# epm_control_1.net
KiCad netlist of a schematic drawn in Altium Designer
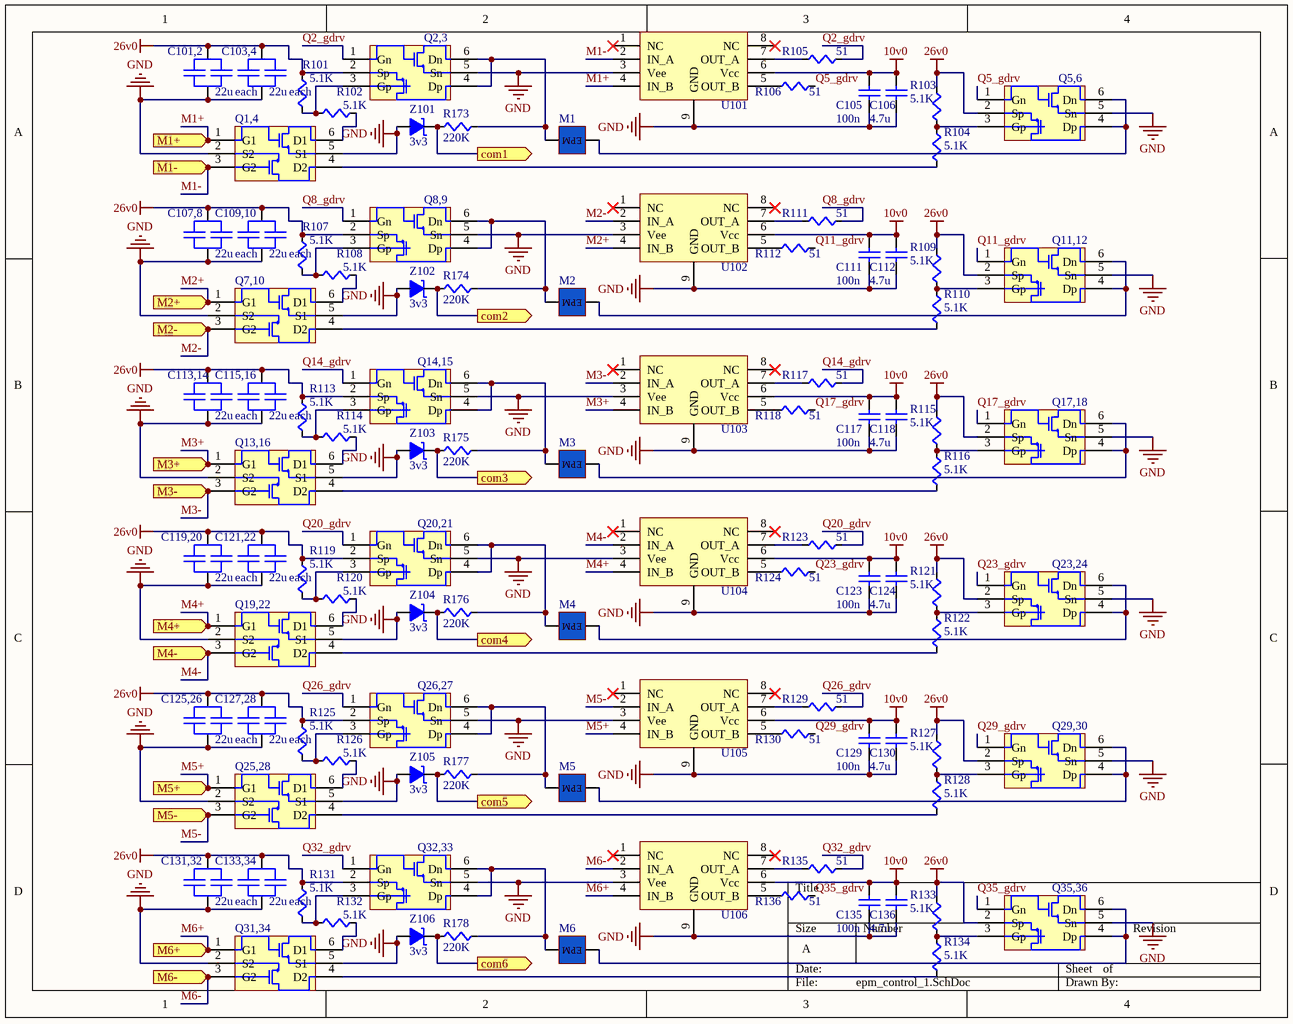
[diagram p0: epm_control_1.SchDoc]

(export (version "E")
  (design (tool "Eeschema 10.0.6"))
  (components
    (comp (ref "C101,2")
      (value "22u")
      (footprint "dicap_smd_1206")
      (fields (field (name "Comment") "Dicap"))
      (libsource (lib "Components") (part "Dicap"))
    )
    (comp (ref "C103,4")
      (value "22u")
      (footprint "dicap_smd_1206")
      (fields (field (name "Comment") "Dicap"))
      (libsource (lib "Components") (part "Dicap"))
    )
    (comp (ref "C105")
      (value "100n")
      (footprint "SMD0603_cap")
      (description "Ceramic Chip Capacitor")
      (fields (field (name "Comment") "Cap"))
      (libsource (lib "Components") (part "Capacitor Ceramic"))
    )
    (comp (ref "C106")
      (value "4.7u")
      (footprint "SMD0603_cap")
      (description "Ceramic Chip Capacitor")
      (fields (field (name "Comment") "Cap"))
      (libsource (lib "Components") (part "Capacitor Ceramic"))
    )
    (comp (ref "C107,8")
      (value "22u")
      (footprint "dicap_smd_1206")
      (fields (field (name "Comment") "Dicap"))
      (libsource (lib "Components") (part "Dicap"))
    )
    (comp (ref "C109,10")
      (value "22u")
      (footprint "dicap_smd_1206")
      (fields (field (name "Comment") "Dicap"))
      (libsource (lib "Components") (part "Dicap"))
    )
    (comp (ref "C111")
      (value "100n")
      (footprint "SMD0603_cap")
      (description "Ceramic Chip Capacitor")
      (fields (field (name "Comment") "Cap"))
      (libsource (lib "Components") (part "Capacitor Ceramic"))
    )
    (comp (ref "C112")
      (value "4.7u")
      (footprint "SMD0603_cap")
      (description "Ceramic Chip Capacitor")
      (fields (field (name "Comment") "Cap"))
      (libsource (lib "Components") (part "Capacitor Ceramic"))
    )
    (comp (ref "C113,14")
      (value "22u")
      (footprint "dicap_smd_1206")
      (fields (field (name "Comment") "Dicap"))
      (libsource (lib "Components") (part "Dicap"))
    )
    (comp (ref "C115,16")
      (value "22u")
      (footprint "dicap_smd_1206")
      (fields (field (name "Comment") "Dicap"))
      (libsource (lib "Components") (part "Dicap"))
    )
    (comp (ref "C117")
      (value "100n")
      (footprint "SMD0603_cap")
      (description "Ceramic Chip Capacitor")
      (fields (field (name "Comment") "Cap"))
      (libsource (lib "Components") (part "Capacitor Ceramic"))
    )
    (comp (ref "C118")
      (value "4.7u")
      (footprint "SMD0603_cap")
      (description "Ceramic Chip Capacitor")
      (fields (field (name "Comment") "Cap"))
      (libsource (lib "Components") (part "Capacitor Ceramic"))
    )
    (comp (ref "C119,20")
      (value "22u")
      (footprint "dicap_smd_1206")
      (fields (field (name "Comment") "Dicap"))
      (libsource (lib "Components") (part "Dicap"))
    )
    (comp (ref "C121,22")
      (value "22u")
      (footprint "dicap_smd_1206")
      (fields (field (name "Comment") "Dicap"))
      (libsource (lib "Components") (part "Dicap"))
    )
    (comp (ref "C123")
      (value "100n")
      (footprint "SMD0603_cap")
      (description "Ceramic Chip Capacitor")
      (fields (field (name "Comment") "Cap"))
      (libsource (lib "Components") (part "Capacitor Ceramic"))
    )
    (comp (ref "C124")
      (value "4.7u")
      (footprint "SMD0603_cap")
      (description "Ceramic Chip Capacitor")
      (fields (field (name "Comment") "Cap"))
      (libsource (lib "Components") (part "Capacitor Ceramic"))
    )
    (comp (ref "C125,26")
      (value "22u")
      (footprint "dicap_smd_1206")
      (fields (field (name "Comment") "Dicap"))
      (libsource (lib "Components") (part "Dicap"))
    )
    (comp (ref "C127,28")
      (value "22u")
      (footprint "dicap_smd_1206")
      (fields (field (name "Comment") "Dicap"))
      (libsource (lib "Components") (part "Dicap"))
    )
    (comp (ref "C129")
      (value "100n")
      (footprint "SMD0603_cap")
      (description "Ceramic Chip Capacitor")
      (fields (field (name "Comment") "Cap"))
      (libsource (lib "Components") (part "Capacitor Ceramic"))
    )
    (comp (ref "C130")
      (value "4.7u")
      (footprint "SMD0603_cap")
      (description "Ceramic Chip Capacitor")
      (fields (field (name "Comment") "Cap"))
      (libsource (lib "Components") (part "Capacitor Ceramic"))
    )
    (comp (ref "C131,32")
      (value "22u")
      (footprint "dicap_smd_1206")
      (fields (field (name "Comment") "Dicap"))
      (libsource (lib "Components") (part "Dicap"))
    )
    (comp (ref "C133,34")
      (value "22u")
      (footprint "dicap_smd_1206")
      (fields (field (name "Comment") "Dicap"))
      (libsource (lib "Components") (part "Dicap"))
    )
    (comp (ref "C135")
      (value "100n")
      (footprint "SMD0603_cap")
      (description "Ceramic Chip Capacitor")
      (fields (field (name "Comment") "Cap"))
      (libsource (lib "Components") (part "Capacitor Ceramic"))
    )
    (comp (ref "C136")
      (value "4.7u")
      (footprint "SMD0603_cap")
      (description "Ceramic Chip Capacitor")
      (fields (field (name "Comment") "Cap"))
      (libsource (lib "Components") (part "Capacitor Ceramic"))
    )
    (comp (ref "M1") (value "EPM") (footprint "40awg_epm") (libsource (lib "Components") (part "EPM")))
    (comp (ref "M2") (value "EPM") (footprint "40awg_epm") (libsource (lib "Components") (part "EPM")))
    (comp (ref "M3") (value "EPM") (footprint "40awg_epm") (libsource (lib "Components") (part "EPM")))
    (comp (ref "M4") (value "EPM") (footprint "40awg_epm") (libsource (lib "Components") (part "EPM")))
    (comp (ref "M5") (value "EPM") (footprint "40awg_epm") (libsource (lib "Components") (part "EPM")))
    (comp (ref "M6") (value "EPM") (footprint "40awg_epm") (libsource (lib "Components") (part "EPM")))
    (comp (ref "Q1,4") (value "SI3292") (footprint "sot23-6l") (libsource (lib "Components") (part "SI3292")))
    (comp (ref "Q2,3")
      (value "DMG6602")
      (footprint "sot23-6l")
      (libsource (lib "Components") (part "DMG6602"))
    )
    (comp (ref "Q5,6")
      (value "DMG6602")
      (footprint "sot23-6l")
      (libsource (lib "Components") (part "DMG6602"))
    )
    (comp (ref "Q7,10")
      (value "SI3292")
      (footprint "sot23-6l")
      (libsource (lib "Components") (part "SI3292"))
    )
    (comp (ref "Q8,9")
      (value "DMG6602")
      (footprint "sot23-6l")
      (libsource (lib "Components") (part "DMG6602"))
    )
    (comp (ref "Q11,12")
      (value "DMG6602")
      (footprint "sot23-6l")
      (libsource (lib "Components") (part "DMG6602"))
    )
    (comp (ref "Q13,16")
      (value "SI3292")
      (footprint "sot23-6l")
      (libsource (lib "Components") (part "SI3292"))
    )
    (comp (ref "Q14,15")
      (value "DMG6602")
      (footprint "sot23-6l")
      (libsource (lib "Components") (part "DMG6602"))
    )
    (comp (ref "Q17,18")
      (value "DMG6602")
      (footprint "sot23-6l")
      (libsource (lib "Components") (part "DMG6602"))
    )
    (comp (ref "Q19,22")
      (value "SI3292")
      (footprint "sot23-6l")
      (libsource (lib "Components") (part "SI3292"))
    )
    (comp (ref "Q20,21")
      (value "DMG6602")
      (footprint "sot23-6l")
      (libsource (lib "Components") (part "DMG6602"))
    )
    (comp (ref "Q23,24")
      (value "DMG6602")
      (footprint "sot23-6l")
      (libsource (lib "Components") (part "DMG6602"))
    )
    (comp (ref "Q25,28")
      (value "SI3292")
      (footprint "sot23-6l")
      (libsource (lib "Components") (part "SI3292"))
    )
    (comp (ref "Q26,27")
      (value "DMG6602")
      (footprint "sot23-6l")
      (libsource (lib "Components") (part "DMG6602"))
    )
    (comp (ref "Q29,30")
      (value "DMG6602")
      (footprint "sot23-6l")
      (libsource (lib "Components") (part "DMG6602"))
    )
    (comp (ref "Q31,34")
      (value "SI3292")
      (footprint "sot23-6l")
      (libsource (lib "Components") (part "SI3292"))
    )
    (comp (ref "Q32,33")
      (value "DMG6602")
      (footprint "sot23-6l")
      (libsource (lib "Components") (part "DMG6602"))
    )
    (comp (ref "Q35,36")
      (value "DMG6602")
      (footprint "sot23-6l")
      (libsource (lib "Components") (part "DMG6602"))
    )
    (comp (ref "R101")
      (value "5.1K")
      (footprint "SMD0603")
      (description "Resistor")
      (fields (field (name "Comment") "Res"))
      (libsource (lib "Components") (part "Resistor"))
    )
    (comp (ref "R102")
      (value "5.1K")
      (footprint "SMD0603")
      (description "Resistor")
      (fields (field (name "Comment") "Res"))
      (libsource (lib "Components") (part "Resistor"))
    )
    (comp (ref "R103")
      (value "5.1K")
      (footprint "SMD0603")
      (description "Resistor")
      (fields (field (name "Comment") "Res"))
      (libsource (lib "Components") (part "Resistor"))
    )
    (comp (ref "R104")
      (value "5.1K")
      (footprint "SMD0603")
      (description "Resistor")
      (fields (field (name "Comment") "Res"))
      (libsource (lib "Components") (part "Resistor"))
    )
    (comp (ref "R105")
      (value "51")
      (footprint "SMD0603")
      (description "Resistor")
      (fields (field (name "Comment") "Res"))
      (libsource (lib "Components") (part "Resistor"))
    )
    (comp (ref "R106")
      (value "51")
      (footprint "SMD0603")
      (description "Resistor")
      (fields (field (name "Comment") "Res"))
      (libsource (lib "Components") (part "Resistor"))
    )
    (comp (ref "R107")
      (value "5.1K")
      (footprint "SMD0603")
      (description "Resistor")
      (fields (field (name "Comment") "Res"))
      (libsource (lib "Components") (part "Resistor"))
    )
    (comp (ref "R108")
      (value "5.1K")
      (footprint "SMD0603")
      (description "Resistor")
      (fields (field (name "Comment") "Res"))
      (libsource (lib "Components") (part "Resistor"))
    )
    (comp (ref "R109")
      (value "5.1K")
      (footprint "SMD0603")
      (description "Resistor")
      (fields (field (name "Comment") "Res"))
      (libsource (lib "Components") (part "Resistor"))
    )
    (comp (ref "R110")
      (value "5.1K")
      (footprint "SMD0603")
      (description "Resistor")
      (fields (field (name "Comment") "Res"))
      (libsource (lib "Components") (part "Resistor"))
    )
    (comp (ref "R111")
      (value "51")
      (footprint "SMD0603")
      (description "Resistor")
      (fields (field (name "Comment") "Res"))
      (libsource (lib "Components") (part "Resistor"))
    )
    (comp (ref "R112")
      (value "51")
      (footprint "SMD0603")
      (description "Resistor")
      (fields (field (name "Comment") "Res"))
      (libsource (lib "Components") (part "Resistor"))
    )
    (comp (ref "R113")
      (value "5.1K")
      (footprint "SMD0603")
      (description "Resistor")
      (fields (field (name "Comment") "Res"))
      (libsource (lib "Components") (part "Resistor"))
    )
    (comp (ref "R114")
      (value "5.1K")
      (footprint "SMD0603")
      (description "Resistor")
      (fields (field (name "Comment") "Res"))
      (libsource (lib "Components") (part "Resistor"))
    )
    (comp (ref "R115")
      (value "5.1K")
      (footprint "SMD0603")
      (description "Resistor")
      (fields (field (name "Comment") "Res"))
      (libsource (lib "Components") (part "Resistor"))
    )
    (comp (ref "R116")
      (value "5.1K")
      (footprint "SMD0603")
      (description "Resistor")
      (fields (field (name "Comment") "Res"))
      (libsource (lib "Components") (part "Resistor"))
    )
    (comp (ref "R117")
      (value "51")
      (footprint "SMD0603")
      (description "Resistor")
      (fields (field (name "Comment") "Res"))
      (libsource (lib "Components") (part "Resistor"))
    )
    (comp (ref "R118")
      (value "51")
      (footprint "SMD0603")
      (description "Resistor")
      (fields (field (name "Comment") "Res"))
      (libsource (lib "Components") (part "Resistor"))
    )
    (comp (ref "R119")
      (value "5.1K")
      (footprint "SMD0603")
      (description "Resistor")
      (fields (field (name "Comment") "Res"))
      (libsource (lib "Components") (part "Resistor"))
    )
    (comp (ref "R120")
      (value "5.1K")
      (footprint "SMD0603")
      (description "Resistor")
      (fields (field (name "Comment") "Res"))
      (libsource (lib "Components") (part "Resistor"))
    )
    (comp (ref "R121")
      (value "5.1K")
      (footprint "SMD0603")
      (description "Resistor")
      (fields (field (name "Comment") "Res"))
      (libsource (lib "Components") (part "Resistor"))
    )
    (comp (ref "R122")
      (value "5.1K")
      (footprint "SMD0603")
      (description "Resistor")
      (fields (field (name "Comment") "Res"))
      (libsource (lib "Components") (part "Resistor"))
    )
    (comp (ref "R123")
      (value "51")
      (footprint "SMD0603")
      (description "Resistor")
      (fields (field (name "Comment") "Res"))
      (libsource (lib "Components") (part "Resistor"))
    )
    (comp (ref "R124")
      (value "51")
      (footprint "SMD0603")
      (description "Resistor")
      (fields (field (name "Comment") "Res"))
      (libsource (lib "Components") (part "Resistor"))
    )
    (comp (ref "R125")
      (value "5.1K")
      (footprint "SMD0603")
      (description "Resistor")
      (fields (field (name "Comment") "Res"))
      (libsource (lib "Components") (part "Resistor"))
    )
    (comp (ref "R126")
      (value "5.1K")
      (footprint "SMD0603")
      (description "Resistor")
      (fields (field (name "Comment") "Res"))
      (libsource (lib "Components") (part "Resistor"))
    )
    (comp (ref "R127")
      (value "5.1K")
      (footprint "SMD0603")
      (description "Resistor")
      (fields (field (name "Comment") "Res"))
      (libsource (lib "Components") (part "Resistor"))
    )
    (comp (ref "R128")
      (value "5.1K")
      (footprint "SMD0603")
      (description "Resistor")
      (fields (field (name "Comment") "Res"))
      (libsource (lib "Components") (part "Resistor"))
    )
    (comp (ref "R129")
      (value "51")
      (footprint "SMD0603")
      (description "Resistor")
      (fields (field (name "Comment") "Res"))
      (libsource (lib "Components") (part "Resistor"))
    )
    (comp (ref "R130")
      (value "51")
      (footprint "SMD0603")
      (description "Resistor")
      (fields (field (name "Comment") "Res"))
      (libsource (lib "Components") (part "Resistor"))
    )
    (comp (ref "R131")
      (value "5.1K")
      (footprint "SMD0603")
      (description "Resistor")
      (fields (field (name "Comment") "Res"))
      (libsource (lib "Components") (part "Resistor"))
    )
    (comp (ref "R132")
      (value "5.1K")
      (footprint "SMD0603")
      (description "Resistor")
      (fields (field (name "Comment") "Res"))
      (libsource (lib "Components") (part "Resistor"))
    )
    (comp (ref "R133")
      (value "5.1K")
      (footprint "SMD0603")
      (description "Resistor")
      (fields (field (name "Comment") "Res"))
      (libsource (lib "Components") (part "Resistor"))
    )
    (comp (ref "R134")
      (value "5.1K")
      (footprint "SMD0603")
      (description "Resistor")
      (fields (field (name "Comment") "Res"))
      (libsource (lib "Components") (part "Resistor"))
    )
    (comp (ref "R135")
      (value "51")
      (footprint "SMD0603")
      (description "Resistor")
      (fields (field (name "Comment") "Res"))
      (libsource (lib "Components") (part "Resistor"))
    )
    (comp (ref "R136")
      (value "51")
      (footprint "SMD0603")
      (description "Resistor")
      (fields (field (name "Comment") "Res"))
      (libsource (lib "Components") (part "Resistor"))
    )
    (comp (ref "R173")
      (value "220K")
      (footprint "SMD0603")
      (description "Resistor")
      (fields (field (name "Comment") "Res"))
      (libsource (lib "Components") (part "Resistor"))
    )
    (comp (ref "R174")
      (value "220K")
      (footprint "SMD0603")
      (description "Resistor")
      (fields (field (name "Comment") "Res"))
      (libsource (lib "Components") (part "Resistor"))
    )
    (comp (ref "R175")
      (value "220K")
      (footprint "SMD0603")
      (description "Resistor")
      (fields (field (name "Comment") "Res"))
      (libsource (lib "Components") (part "Resistor"))
    )
    (comp (ref "R176")
      (value "220K")
      (footprint "SMD0603")
      (description "Resistor")
      (fields (field (name "Comment") "Res"))
      (libsource (lib "Components") (part "Resistor"))
    )
    (comp (ref "R177")
      (value "220K")
      (footprint "SMD0603")
      (description "Resistor")
      (fields (field (name "Comment") "Res"))
      (libsource (lib "Components") (part "Resistor"))
    )
    (comp (ref "R178")
      (value "220K")
      (footprint "SMD0603")
      (description "Resistor")
      (fields (field (name "Comment") "Res"))
      (libsource (lib "Components") (part "Resistor"))
    )
    (comp (ref "U101")
      (value "LM5111-1")
      (footprint "tssop-8")
      (libsource (lib "Components") (part "LM5111-1"))
    )
    (comp (ref "U102")
      (value "LM5111-1")
      (footprint "tssop-8")
      (libsource (lib "Components") (part "LM5111-1"))
    )
    (comp (ref "U103")
      (value "LM5111-1")
      (footprint "tssop-8")
      (libsource (lib "Components") (part "LM5111-1"))
    )
    (comp (ref "U104")
      (value "LM5111-1")
      (footprint "tssop-8")
      (libsource (lib "Components") (part "LM5111-1"))
    )
    (comp (ref "U105")
      (value "LM5111-1")
      (footprint "tssop-8")
      (libsource (lib "Components") (part "LM5111-1"))
    )
    (comp (ref "U106")
      (value "LM5111-1")
      (footprint "tssop-8")
      (libsource (lib "Components") (part "LM5111-1"))
    )
    (comp (ref "Z101")
      (value "3v3")
      (footprint "SOD-323F")
      (fields (field (name "Comment") "Zener"))
      (libsource (lib "Components") (part "Zener"))
    )
    (comp (ref "Z102")
      (value "3v3")
      (footprint "SOD-323F")
      (fields (field (name "Comment") "Zener"))
      (libsource (lib "Components") (part "Zener"))
    )
    (comp (ref "Z103")
      (value "3v3")
      (footprint "SOD-323F")
      (fields (field (name "Comment") "Zener"))
      (libsource (lib "Components") (part "Zener"))
    )
    (comp (ref "Z104")
      (value "3v3")
      (footprint "SOD-323F")
      (fields (field (name "Comment") "Zener"))
      (libsource (lib "Components") (part "Zener"))
    )
    (comp (ref "Z105")
      (value "3v3")
      (footprint "SOD-323F")
      (fields (field (name "Comment") "Zener"))
      (libsource (lib "Components") (part "Zener"))
    )
    (comp (ref "Z106")
      (value "3v3")
      (footprint "SOD-323F")
      (fields (field (name "Comment") "Zener"))
      (libsource (lib "Components") (part "Zener"))
    )
  )
  (nets
    (net (code "1") (name "/M1+") (class "Default")
      (node (ref "Q1,4") (pin "1") (pinfunction "G1_1") (pintype "passive"))
      (node (ref "U101") (pin "4") (pinfunction "IN_B_4") (pintype "passive"))
    )
    (net (code "2") (name "/M1-") (class "Default")
      (node (ref "Q1,4") (pin "3") (pinfunction "G2_3") (pintype "passive"))
      (node (ref "U101") (pin "2") (pinfunction "IN_A_2") (pintype "passive"))
    )
    (net (code "3") (name "/M2+") (class "Default")
      (node (ref "Q7,10") (pin "1") (pinfunction "G1_1") (pintype "passive"))
      (node (ref "U102") (pin "4") (pinfunction "IN_B_4") (pintype "passive"))
    )
    (net (code "4") (name "/M2-") (class "Default")
      (node (ref "Q7,10") (pin "3") (pinfunction "G2_3") (pintype "passive"))
      (node (ref "U102") (pin "2") (pinfunction "IN_A_2") (pintype "passive"))
    )
    (net (code "5") (name "/M3+") (class "Default")
      (node (ref "Q13,16") (pin "1") (pinfunction "G1_1") (pintype "passive"))
      (node (ref "U103") (pin "4") (pinfunction "IN_B_4") (pintype "passive"))
    )
    (net (code "6") (name "/M3-") (class "Default")
      (node (ref "Q13,16") (pin "3") (pinfunction "G2_3") (pintype "passive"))
      (node (ref "U103") (pin "2") (pinfunction "IN_A_2") (pintype "passive"))
    )
    (net (code "7") (name "/M4+") (class "Default")
      (node (ref "Q19,22") (pin "1") (pinfunction "G1_1") (pintype "passive"))
      (node (ref "U104") (pin "4") (pinfunction "IN_B_4") (pintype "passive"))
    )
    (net (code "8") (name "/M4-") (class "Default")
      (node (ref "Q19,22") (pin "3") (pinfunction "G2_3") (pintype "passive"))
      (node (ref "U104") (pin "2") (pinfunction "IN_A_2") (pintype "passive"))
    )
    (net (code "9") (name "/M5+") (class "Default")
      (node (ref "Q25,28") (pin "1") (pinfunction "G1_1") (pintype "passive"))
      (node (ref "U105") (pin "4") (pinfunction "IN_B_4") (pintype "passive"))
    )
    (net (code "10") (name "/M5-") (class "Default")
      (node (ref "Q25,28") (pin "3") (pinfunction "G2_3") (pintype "passive"))
      (node (ref "U105") (pin "2") (pinfunction "IN_A_2") (pintype "passive"))
    )
    (net (code "11") (name "/M6+") (class "Default")
      (node (ref "Q31,34") (pin "1") (pinfunction "G1_1") (pintype "passive"))
      (node (ref "U106") (pin "4") (pinfunction "IN_B_4") (pintype "passive"))
    )
    (net (code "12") (name "/M6-") (class "Default")
      (node (ref "Q31,34") (pin "3") (pinfunction "G2_3") (pintype "passive"))
      (node (ref "U106") (pin "2") (pinfunction "IN_A_2") (pintype "passive"))
    )
    (net (code "13") (name "/Q2_gdrv") (class "Default")
      (node (ref "Q2,3") (pin "1") (pinfunction "Gn_1") (pintype "passive"))
      (node (ref "R105") (pin "1") (pinfunction "1_1") (pintype "passive"))
    )
    (net (code "14") (name "/Q5_gdrv") (class "Default")
      (node (ref "Q5,6") (pin "1") (pinfunction "Gn_1") (pintype "passive"))
      (node (ref "R106") (pin "1") (pinfunction "1_1") (pintype "passive"))
    )
    (net (code "15") (name "/Q8_gdrv") (class "Default")
      (node (ref "Q8,9") (pin "1") (pinfunction "Gn_1") (pintype "passive"))
      (node (ref "R111") (pin "1") (pinfunction "1_1") (pintype "passive"))
    )
    (net (code "16") (name "/Q11_gdrv") (class "Default")
      (node (ref "Q11,12") (pin "1") (pinfunction "Gn_1") (pintype "passive"))
      (node (ref "R112") (pin "1") (pinfunction "1_1") (pintype "passive"))
    )
    (net (code "17") (name "/Q14_gdrv") (class "Default")
      (node (ref "Q14,15") (pin "1") (pinfunction "Gn_1") (pintype "passive"))
      (node (ref "R117") (pin "1") (pinfunction "1_1") (pintype "passive"))
    )
    (net (code "18") (name "/Q17_gdrv") (class "Default")
      (node (ref "Q17,18") (pin "1") (pinfunction "Gn_1") (pintype "passive"))
      (node (ref "R118") (pin "1") (pinfunction "1_1") (pintype "passive"))
    )
    (net (code "19") (name "/Q20_gdrv") (class "Default")
      (node (ref "Q20,21") (pin "1") (pinfunction "Gn_1") (pintype "passive"))
      (node (ref "R123") (pin "1") (pinfunction "1_1") (pintype "passive"))
    )
    (net (code "20") (name "/Q23_gdrv") (class "Default")
      (node (ref "Q23,24") (pin "1") (pinfunction "Gn_1") (pintype "passive"))
      (node (ref "R124") (pin "1") (pinfunction "1_1") (pintype "passive"))
    )
    (net (code "21") (name "/Q26_gdrv") (class "Default")
      (node (ref "Q26,27") (pin "1") (pinfunction "Gn_1") (pintype "passive"))
      (node (ref "R129") (pin "1") (pinfunction "1_1") (pintype "passive"))
    )
    (net (code "22") (name "/Q29_gdrv") (class "Default")
      (node (ref "Q29,30") (pin "1") (pinfunction "Gn_1") (pintype "passive"))
      (node (ref "R130") (pin "1") (pinfunction "1_1") (pintype "passive"))
    )
    (net (code "23") (name "/Q32_gdrv") (class "Default")
      (node (ref "Q32,33") (pin "1") (pinfunction "Gn_1") (pintype "passive"))
      (node (ref "R135") (pin "1") (pinfunction "1_1") (pintype "passive"))
    )
    (net (code "24") (name "/Q35_gdrv") (class "Default")
      (node (ref "Q35,36") (pin "1") (pinfunction "Gn_1") (pintype "passive"))
      (node (ref "R136") (pin "1") (pinfunction "1_1") (pintype "passive"))
    )
    (net (code "25") (name "/com1") (class "Default")
      (node (ref "R173") (pin "1") (pinfunction "1_1") (pintype "passive"))
      (node (ref "Z101") (pin "K") (pinfunction "2_K") (pintype "passive"))
    )
    (net (code "26") (name "/com2") (class "Default")
      (node (ref "R174") (pin "1") (pinfunction "1_1") (pintype "passive"))
      (node (ref "Z102") (pin "K") (pinfunction "2_K") (pintype "passive"))
    )
    (net (code "27") (name "/com3") (class "Default")
      (node (ref "R175") (pin "1") (pinfunction "1_1") (pintype "passive"))
      (node (ref "Z103") (pin "K") (pinfunction "2_K") (pintype "passive"))
    )
    (net (code "28") (name "/com4") (class "Default")
      (node (ref "R176") (pin "1") (pinfunction "1_1") (pintype "passive"))
      (node (ref "Z104") (pin "K") (pinfunction "2_K") (pintype "passive"))
    )
    (net (code "29") (name "/com5") (class "Default")
      (node (ref "R177") (pin "1") (pinfunction "1_1") (pintype "passive"))
      (node (ref "Z105") (pin "K") (pinfunction "2_K") (pintype "passive"))
    )
    (net (code "30") (name "/com6") (class "Default")
      (node (ref "R178") (pin "1") (pinfunction "1_1") (pintype "passive"))
      (node (ref "Z106") (pin "K") (pinfunction "2_K") (pintype "passive"))
    )
    (net (code "31") (name "10v0") (class "Default")
      (node (ref "C105") (pin "2") (pinfunction "2_2") (pintype "passive"))
      (node (ref "C106") (pin "2") (pinfunction "2_2") (pintype "passive"))
      (node (ref "C111") (pin "2") (pinfunction "2_2") (pintype "passive"))
      (node (ref "C112") (pin "2") (pinfunction "2_2") (pintype "passive"))
      (node (ref "C117") (pin "2") (pinfunction "2_2") (pintype "passive"))
      (node (ref "C118") (pin "2") (pinfunction "2_2") (pintype "passive"))
      (node (ref "C123") (pin "2") (pinfunction "2_2") (pintype "passive"))
      (node (ref "C124") (pin "2") (pinfunction "2_2") (pintype "passive"))
      (node (ref "C129") (pin "2") (pinfunction "2_2") (pintype "passive"))
      (node (ref "C130") (pin "2") (pinfunction "2_2") (pintype "passive"))
      (node (ref "C135") (pin "2") (pinfunction "2_2") (pintype "passive"))
      (node (ref "C136") (pin "2") (pinfunction "2_2") (pintype "passive"))
      (node (ref "U101") (pin "6") (pinfunction "Vcc_6") (pintype "passive"))
      (node (ref "U102") (pin "6") (pinfunction "Vcc_6") (pintype "passive"))
      (node (ref "U103") (pin "6") (pinfunction "Vcc_6") (pintype "passive"))
      (node (ref "U104") (pin "6") (pinfunction "Vcc_6") (pintype "passive"))
      (node (ref "U105") (pin "6") (pinfunction "Vcc_6") (pintype "passive"))
      (node (ref "U106") (pin "6") (pinfunction "Vcc_6") (pintype "passive"))
    )
    (net (code "32") (name "26v0") (class "Default")
      (node (ref "C101,2") (pin "2") (pinfunction "2_2") (pintype "passive"))
      (node (ref "C103,4") (pin "2") (pinfunction "2_2") (pintype "passive"))
      (node (ref "C107,8") (pin "2") (pinfunction "2_2") (pintype "passive"))
      (node (ref "C109,10") (pin "2") (pinfunction "2_2") (pintype "passive"))
      (node (ref "C113,14") (pin "2") (pinfunction "2_2") (pintype "passive"))
      (node (ref "C115,16") (pin "2") (pinfunction "2_2") (pintype "passive"))
      (node (ref "C119,20") (pin "2") (pinfunction "2_2") (pintype "passive"))
      (node (ref "C121,22") (pin "2") (pinfunction "2_2") (pintype "passive"))
      (node (ref "C125,26") (pin "2") (pinfunction "2_2") (pintype "passive"))
      (node (ref "C127,28") (pin "2") (pinfunction "2_2") (pintype "passive"))
      (node (ref "C131,32") (pin "2") (pinfunction "2_2") (pintype "passive"))
      (node (ref "C133,34") (pin "2") (pinfunction "2_2") (pintype "passive"))
      (node (ref "Q11,12") (pin "2") (pinfunction "Sp_2") (pintype "passive"))
      (node (ref "Q14,15") (pin "2") (pinfunction "Sp_2") (pintype "passive"))
      (node (ref "Q17,18") (pin "2") (pinfunction "Sp_2") (pintype "passive"))
      (node (ref "Q2,3") (pin "2") (pinfunction "Sp_2") (pintype "passive"))
      (node (ref "Q20,21") (pin "2") (pinfunction "Sp_2") (pintype "passive"))
      (node (ref "Q23,24") (pin "2") (pinfunction "Sp_2") (pintype "passive"))
      (node (ref "Q26,27") (pin "2") (pinfunction "Sp_2") (pintype "passive"))
      (node (ref "Q29,30") (pin "2") (pinfunction "Sp_2") (pintype "passive"))
      (node (ref "Q32,33") (pin "2") (pinfunction "Sp_2") (pintype "passive"))
      (node (ref "Q35,36") (pin "2") (pinfunction "Sp_2") (pintype "passive"))
      (node (ref "Q5,6") (pin "2") (pinfunction "Sp_2") (pintype "passive"))
      (node (ref "Q8,9") (pin "2") (pinfunction "Sp_2") (pintype "passive"))
      (node (ref "R101") (pin "2") (pinfunction "2_2") (pintype "passive"))
      (node (ref "R103") (pin "2") (pinfunction "2_2") (pintype "passive"))
      (node (ref "R107") (pin "2") (pinfunction "2_2") (pintype "passive"))
      (node (ref "R109") (pin "2") (pinfunction "2_2") (pintype "passive"))
      (node (ref "R113") (pin "2") (pinfunction "2_2") (pintype "passive"))
      (node (ref "R115") (pin "2") (pinfunction "2_2") (pintype "passive"))
      (node (ref "R119") (pin "2") (pinfunction "2_2") (pintype "passive"))
      (node (ref "R121") (pin "2") (pinfunction "2_2") (pintype "passive"))
      (node (ref "R125") (pin "2") (pinfunction "2_2") (pintype "passive"))
      (node (ref "R127") (pin "2") (pinfunction "2_2") (pintype "passive"))
      (node (ref "R131") (pin "2") (pinfunction "2_2") (pintype "passive"))
      (node (ref "R133") (pin "2") (pinfunction "2_2") (pintype "passive"))
    )
    (net (code "33") (name "GND") (class "Default")
      (node (ref "C101,2") (pin "1") (pinfunction "1_1") (pintype "passive"))
      (node (ref "C103,4") (pin "1") (pinfunction "1_1") (pintype "passive"))
      (node (ref "C105") (pin "1") (pinfunction "1_1") (pintype "passive"))
      (node (ref "C106") (pin "1") (pinfunction "1_1") (pintype "passive"))
      (node (ref "C107,8") (pin "1") (pinfunction "1_1") (pintype "passive"))
      (node (ref "C109,10") (pin "1") (pinfunction "1_1") (pintype "passive"))
      (node (ref "C111") (pin "1") (pinfunction "1_1") (pintype "passive"))
      (node (ref "C112") (pin "1") (pinfunction "1_1") (pintype "passive"))
      (node (ref "C113,14") (pin "1") (pinfunction "1_1") (pintype "passive"))
      (node (ref "C115,16") (pin "1") (pinfunction "1_1") (pintype "passive"))
      (node (ref "C117") (pin "1") (pinfunction "1_1") (pintype "passive"))
      (node (ref "C118") (pin "1") (pinfunction "1_1") (pintype "passive"))
      (node (ref "C119,20") (pin "1") (pinfunction "1_1") (pintype "passive"))
      (node (ref "C121,22") (pin "1") (pinfunction "1_1") (pintype "passive"))
      (node (ref "C123") (pin "1") (pinfunction "1_1") (pintype "passive"))
      (node (ref "C124") (pin "1") (pinfunction "1_1") (pintype "passive"))
      (node (ref "C125,26") (pin "1") (pinfunction "1_1") (pintype "passive"))
      (node (ref "C127,28") (pin "1") (pinfunction "1_1") (pintype "passive"))
      (node (ref "C129") (pin "1") (pinfunction "1_1") (pintype "passive"))
      (node (ref "C130") (pin "1") (pinfunction "1_1") (pintype "passive"))
      (node (ref "C131,32") (pin "1") (pinfunction "1_1") (pintype "passive"))
      (node (ref "C133,34") (pin "1") (pinfunction "1_1") (pintype "passive"))
      (node (ref "C135") (pin "1") (pinfunction "1_1") (pintype "passive"))
      (node (ref "C136") (pin "1") (pinfunction "1_1") (pintype "passive"))
      (node (ref "Q1,4") (pin "2") (pinfunction "S2_2") (pintype "passive"))
      (node (ref "Q1,4") (pin "5") (pinfunction "S1_5") (pintype "passive"))
      (node (ref "Q11,12") (pin "5") (pinfunction "Sn_5") (pintype "passive"))
      (node (ref "Q13,16") (pin "2") (pinfunction "S2_2") (pintype "passive"))
      (node (ref "Q13,16") (pin "5") (pinfunction "S1_5") (pintype "passive"))
      (node (ref "Q14,15") (pin "5") (pinfunction "Sn_5") (pintype "passive"))
      (node (ref "Q17,18") (pin "5") (pinfunction "Sn_5") (pintype "passive"))
      (node (ref "Q19,22") (pin "2") (pinfunction "S2_2") (pintype "passive"))
      (node (ref "Q19,22") (pin "5") (pinfunction "S1_5") (pintype "passive"))
      (node (ref "Q2,3") (pin "5") (pinfunction "Sn_5") (pintype "passive"))
      (node (ref "Q20,21") (pin "5") (pinfunction "Sn_5") (pintype "passive"))
      (node (ref "Q23,24") (pin "5") (pinfunction "Sn_5") (pintype "passive"))
      (node (ref "Q25,28") (pin "2") (pinfunction "S2_2") (pintype "passive"))
      (node (ref "Q25,28") (pin "5") (pinfunction "S1_5") (pintype "passive"))
      (node (ref "Q26,27") (pin "5") (pinfunction "Sn_5") (pintype "passive"))
      (node (ref "Q29,30") (pin "5") (pinfunction "Sn_5") (pintype "passive"))
      (node (ref "Q31,34") (pin "2") (pinfunction "S2_2") (pintype "passive"))
      (node (ref "Q31,34") (pin "5") (pinfunction "S1_5") (pintype "passive"))
      (node (ref "Q32,33") (pin "5") (pinfunction "Sn_5") (pintype "passive"))
      (node (ref "Q35,36") (pin "5") (pinfunction "Sn_5") (pintype "passive"))
      (node (ref "Q5,6") (pin "5") (pinfunction "Sn_5") (pintype "passive"))
      (node (ref "Q7,10") (pin "2") (pinfunction "S2_2") (pintype "passive"))
      (node (ref "Q7,10") (pin "5") (pinfunction "S1_5") (pintype "passive"))
      (node (ref "Q8,9") (pin "5") (pinfunction "Sn_5") (pintype "passive"))
      (node (ref "U101") (pin "3") (pinfunction "Vee_3") (pintype "passive"))
      (node (ref "U101") (pin "9") (pinfunction "GND_9") (pintype "passive"))
      (node (ref "U102") (pin "3") (pinfunction "Vee_3") (pintype "passive"))
      (node (ref "U102") (pin "9") (pinfunction "GND_9") (pintype "passive"))
      (node (ref "U103") (pin "3") (pinfunction "Vee_3") (pintype "passive"))
      (node (ref "U103") (pin "9") (pinfunction "GND_9") (pintype "passive"))
      (node (ref "U104") (pin "3") (pinfunction "Vee_3") (pintype "passive"))
      (node (ref "U104") (pin "9") (pinfunction "GND_9") (pintype "passive"))
      (node (ref "U105") (pin "3") (pinfunction "Vee_3") (pintype "passive"))
      (node (ref "U105") (pin "9") (pinfunction "GND_9") (pintype "passive"))
      (node (ref "U106") (pin "3") (pinfunction "Vee_3") (pintype "passive"))
      (node (ref "U106") (pin "9") (pinfunction "GND_9") (pintype "passive"))
      (node (ref "Z101") (pin "A") (pintype "passive"))
      (node (ref "Z102") (pin "A") (pintype "passive"))
      (node (ref "Z103") (pin "A") (pintype "passive"))
      (node (ref "Z104") (pin "A") (pintype "passive"))
      (node (ref "Z105") (pin "A") (pintype "passive"))
      (node (ref "Z106") (pin "A") (pintype "passive"))
    )
    (net (code "34") (name "Net-(Q1,4-D1)") (class "Default")
      (node (ref "Q1,4") (pin "6") (pinfunction "D1_6") (pintype "passive"))
      (node (ref "R102") (pin "1") (pinfunction "1_1") (pintype "passive"))
    )
    (net (code "35") (name "Net-(Q1,4-D2)") (class "Default")
      (node (ref "Q1,4") (pin "4") (pinfunction "D2_4") (pintype "passive"))
      (node (ref "R104") (pin "1") (pinfunction "1_1") (pintype "passive"))
    )
    (net (code "36") (name "Net-(Q2,3-Dn)") (class "Default")
      (node (ref "M1") (pin "2") (pinfunction "2_2") (pintype "passive"))
      (node (ref "Q2,3") (pin "4") (pinfunction "Dp_4") (pintype "passive"))
      (node (ref "Q2,3") (pin "6") (pinfunction "Dn_6") (pintype "passive"))
      (node (ref "R173") (pin "2") (pinfunction "2_2") (pintype "passive"))
    )
    (net (code "37") (name "Net-(Q2,3-Gp)") (class "Default")
      (node (ref "Q2,3") (pin "3") (pinfunction "Gp_3") (pintype "passive"))
      (node (ref "R101") (pin "1") (pinfunction "1_1") (pintype "passive"))
      (node (ref "R102") (pin "2") (pinfunction "2_2") (pintype "passive"))
    )
    (net (code "38") (name "Net-(Q5,6-Dn)") (class "Default")
      (node (ref "M1") (pin "1") (pinfunction "1_1") (pintype "passive"))
      (node (ref "Q5,6") (pin "4") (pinfunction "Dp_4") (pintype "passive"))
      (node (ref "Q5,6") (pin "6") (pinfunction "Dn_6") (pintype "passive"))
    )
    (net (code "39") (name "Net-(Q5,6-Gp)") (class "Default")
      (node (ref "Q5,6") (pin "3") (pinfunction "Gp_3") (pintype "passive"))
      (node (ref "R103") (pin "1") (pinfunction "1_1") (pintype "passive"))
      (node (ref "R104") (pin "2") (pinfunction "2_2") (pintype "passive"))
    )
    (net (code "40") (name "Net-(Q7,10-D1)") (class "Default")
      (node (ref "Q7,10") (pin "6") (pinfunction "D1_6") (pintype "passive"))
      (node (ref "R108") (pin "1") (pinfunction "1_1") (pintype "passive"))
    )
    (net (code "41") (name "Net-(Q7,10-D2)") (class "Default")
      (node (ref "Q7,10") (pin "4") (pinfunction "D2_4") (pintype "passive"))
      (node (ref "R110") (pin "1") (pinfunction "1_1") (pintype "passive"))
    )
    (net (code "42") (name "Net-(Q8,9-Dn)") (class "Default")
      (node (ref "M2") (pin "2") (pinfunction "2_2") (pintype "passive"))
      (node (ref "Q8,9") (pin "4") (pinfunction "Dp_4") (pintype "passive"))
      (node (ref "Q8,9") (pin "6") (pinfunction "Dn_6") (pintype "passive"))
      (node (ref "R174") (pin "2") (pinfunction "2_2") (pintype "passive"))
    )
    (net (code "43") (name "Net-(Q8,9-Gp)") (class "Default")
      (node (ref "Q8,9") (pin "3") (pinfunction "Gp_3") (pintype "passive"))
      (node (ref "R107") (pin "1") (pinfunction "1_1") (pintype "passive"))
      (node (ref "R108") (pin "2") (pinfunction "2_2") (pintype "passive"))
    )
    (net (code "44") (name "Net-(Q11,12-Dn)") (class "Default")
      (node (ref "M2") (pin "1") (pinfunction "1_1") (pintype "passive"))
      (node (ref "Q11,12") (pin "4") (pinfunction "Dp_4") (pintype "passive"))
      (node (ref "Q11,12") (pin "6") (pinfunction "Dn_6") (pintype "passive"))
    )
    (net (code "45") (name "Net-(Q11,12-Gp)") (class "Default")
      (node (ref "Q11,12") (pin "3") (pinfunction "Gp_3") (pintype "passive"))
      (node (ref "R109") (pin "1") (pinfunction "1_1") (pintype "passive"))
      (node (ref "R110") (pin "2") (pinfunction "2_2") (pintype "passive"))
    )
    (net (code "46") (name "Net-(Q13,16-D1)") (class "Default")
      (node (ref "Q13,16") (pin "6") (pinfunction "D1_6") (pintype "passive"))
      (node (ref "R114") (pin "1") (pinfunction "1_1") (pintype "passive"))
    )
    (net (code "47") (name "Net-(Q13,16-D2)") (class "Default")
      (node (ref "Q13,16") (pin "4") (pinfunction "D2_4") (pintype "passive"))
      (node (ref "R116") (pin "1") (pinfunction "1_1") (pintype "passive"))
    )
    (net (code "48") (name "Net-(Q14,15-Dn)") (class "Default")
      (node (ref "M3") (pin "2") (pinfunction "2_2") (pintype "passive"))
      (node (ref "Q14,15") (pin "4") (pinfunction "Dp_4") (pintype "passive"))
      (node (ref "Q14,15") (pin "6") (pinfunction "Dn_6") (pintype "passive"))
      (node (ref "R175") (pin "2") (pinfunction "2_2") (pintype "passive"))
    )
    (net (code "49") (name "Net-(Q14,15-Gp)") (class "Default")
      (node (ref "Q14,15") (pin "3") (pinfunction "Gp_3") (pintype "passive"))
      (node (ref "R113") (pin "1") (pinfunction "1_1") (pintype "passive"))
      (node (ref "R114") (pin "2") (pinfunction "2_2") (pintype "passive"))
    )
    (net (code "50") (name "Net-(Q17,18-Dn)") (class "Default")
      (node (ref "M3") (pin "1") (pinfunction "1_1") (pintype "passive"))
      (node (ref "Q17,18") (pin "4") (pinfunction "Dp_4") (pintype "passive"))
      (node (ref "Q17,18") (pin "6") (pinfunction "Dn_6") (pintype "passive"))
    )
    (net (code "51") (name "Net-(Q17,18-Gp)") (class "Default")
      (node (ref "Q17,18") (pin "3") (pinfunction "Gp_3") (pintype "passive"))
      (node (ref "R115") (pin "1") (pinfunction "1_1") (pintype "passive"))
      (node (ref "R116") (pin "2") (pinfunction "2_2") (pintype "passive"))
    )
    (net (code "52") (name "Net-(Q19,22-D1)") (class "Default")
      (node (ref "Q19,22") (pin "6") (pinfunction "D1_6") (pintype "passive"))
      (node (ref "R120") (pin "1") (pinfunction "1_1") (pintype "passive"))
    )
    (net (code "53") (name "Net-(Q19,22-D2)") (class "Default")
      (node (ref "Q19,22") (pin "4") (pinfunction "D2_4") (pintype "passive"))
      (node (ref "R122") (pin "1") (pinfunction "1_1") (pintype "passive"))
    )
    (net (code "54") (name "Net-(Q20,21-Dn)") (class "Default")
      (node (ref "M4") (pin "2") (pinfunction "2_2") (pintype "passive"))
      (node (ref "Q20,21") (pin "4") (pinfunction "Dp_4") (pintype "passive"))
      (node (ref "Q20,21") (pin "6") (pinfunction "Dn_6") (pintype "passive"))
      (node (ref "R176") (pin "2") (pinfunction "2_2") (pintype "passive"))
    )
    (net (code "55") (name "Net-(Q20,21-Gp)") (class "Default")
      (node (ref "Q20,21") (pin "3") (pinfunction "Gp_3") (pintype "passive"))
      (node (ref "R119") (pin "1") (pinfunction "1_1") (pintype "passive"))
      (node (ref "R120") (pin "2") (pinfunction "2_2") (pintype "passive"))
    )
    (net (code "56") (name "Net-(Q23,24-Dn)") (class "Default")
      (node (ref "M4") (pin "1") (pinfunction "1_1") (pintype "passive"))
      (node (ref "Q23,24") (pin "4") (pinfunction "Dp_4") (pintype "passive"))
      (node (ref "Q23,24") (pin "6") (pinfunction "Dn_6") (pintype "passive"))
    )
    (net (code "57") (name "Net-(Q23,24-Gp)") (class "Default")
      (node (ref "Q23,24") (pin "3") (pinfunction "Gp_3") (pintype "passive"))
      (node (ref "R121") (pin "1") (pinfunction "1_1") (pintype "passive"))
      (node (ref "R122") (pin "2") (pinfunction "2_2") (pintype "passive"))
    )
    (net (code "58") (name "Net-(Q25,28-D1)") (class "Default")
      (node (ref "Q25,28") (pin "6") (pinfunction "D1_6") (pintype "passive"))
      (node (ref "R126") (pin "1") (pinfunction "1_1") (pintype "passive"))
    )
    (net (code "59") (name "Net-(Q25,28-D2)") (class "Default")
      (node (ref "Q25,28") (pin "4") (pinfunction "D2_4") (pintype "passive"))
      (node (ref "R128") (pin "1") (pinfunction "1_1") (pintype "passive"))
    )
    (net (code "60") (name "Net-(Q26,27-Dn)") (class "Default")
      (node (ref "M5") (pin "2") (pinfunction "2_2") (pintype "passive"))
      (node (ref "Q26,27") (pin "4") (pinfunction "Dp_4") (pintype "passive"))
      (node (ref "Q26,27") (pin "6") (pinfunction "Dn_6") (pintype "passive"))
      (node (ref "R177") (pin "2") (pinfunction "2_2") (pintype "passive"))
    )
    (net (code "61") (name "Net-(Q26,27-Gp)") (class "Default")
      (node (ref "Q26,27") (pin "3") (pinfunction "Gp_3") (pintype "passive"))
      (node (ref "R125") (pin "1") (pinfunction "1_1") (pintype "passive"))
      (node (ref "R126") (pin "2") (pinfunction "2_2") (pintype "passive"))
    )
    (net (code "62") (name "Net-(Q29,30-Dn)") (class "Default")
      (node (ref "M5") (pin "1") (pinfunction "1_1") (pintype "passive"))
      (node (ref "Q29,30") (pin "4") (pinfunction "Dp_4") (pintype "passive"))
      (node (ref "Q29,30") (pin "6") (pinfunction "Dn_6") (pintype "passive"))
    )
    (net (code "63") (name "Net-(Q29,30-Gp)") (class "Default")
      (node (ref "Q29,30") (pin "3") (pinfunction "Gp_3") (pintype "passive"))
      (node (ref "R127") (pin "1") (pinfunction "1_1") (pintype "passive"))
      (node (ref "R128") (pin "2") (pinfunction "2_2") (pintype "passive"))
    )
    (net (code "64") (name "Net-(Q31,34-D1)") (class "Default")
      (node (ref "Q31,34") (pin "6") (pinfunction "D1_6") (pintype "passive"))
      (node (ref "R132") (pin "1") (pinfunction "1_1") (pintype "passive"))
    )
    (net (code "65") (name "Net-(Q31,34-D2)") (class "Default")
      (node (ref "Q31,34") (pin "4") (pinfunction "D2_4") (pintype "passive"))
      (node (ref "R134") (pin "1") (pinfunction "1_1") (pintype "passive"))
    )
    (net (code "66") (name "Net-(Q32,33-Dn)") (class "Default")
      (node (ref "M6") (pin "2") (pinfunction "2_2") (pintype "passive"))
      (node (ref "Q32,33") (pin "4") (pinfunction "Dp_4") (pintype "passive"))
      (node (ref "Q32,33") (pin "6") (pinfunction "Dn_6") (pintype "passive"))
      (node (ref "R178") (pin "2") (pinfunction "2_2") (pintype "passive"))
    )
    (net (code "67") (name "Net-(Q32,33-Gp)") (class "Default")
      (node (ref "Q32,33") (pin "3") (pinfunction "Gp_3") (pintype "passive"))
      (node (ref "R131") (pin "1") (pinfunction "1_1") (pintype "passive"))
      (node (ref "R132") (pin "2") (pinfunction "2_2") (pintype "passive"))
    )
    (net (code "68") (name "Net-(Q35,36-Dn)") (class "Default")
      (node (ref "M6") (pin "1") (pinfunction "1_1") (pintype "passive"))
      (node (ref "Q35,36") (pin "4") (pinfunction "Dp_4") (pintype "passive"))
      (node (ref "Q35,36") (pin "6") (pinfunction "Dn_6") (pintype "passive"))
    )
    (net (code "69") (name "Net-(Q35,36-Gp)") (class "Default")
      (node (ref "Q35,36") (pin "3") (pinfunction "Gp_3") (pintype "passive"))
      (node (ref "R133") (pin "1") (pinfunction "1_1") (pintype "passive"))
      (node (ref "R134") (pin "2") (pinfunction "2_2") (pintype "passive"))
    )
    (net (code "70") (name "Net-(U101-OUT_A)") (class "Default")
      (node (ref "R105") (pin "2") (pinfunction "2_2") (pintype "passive"))
      (node (ref "U101") (pin "7") (pinfunction "OUT_A_7") (pintype "passive"))
    )
    (net (code "71") (name "Net-(U101-OUT_B)") (class "Default")
      (node (ref "R106") (pin "2") (pinfunction "2_2") (pintype "passive"))
      (node (ref "U101") (pin "5") (pinfunction "OUT_B_5") (pintype "passive"))
    )
    (net (code "72") (name "Net-(U102-OUT_A)") (class "Default")
      (node (ref "R111") (pin "2") (pinfunction "2_2") (pintype "passive"))
      (node (ref "U102") (pin "7") (pinfunction "OUT_A_7") (pintype "passive"))
    )
    (net (code "73") (name "Net-(U102-OUT_B)") (class "Default")
      (node (ref "R112") (pin "2") (pinfunction "2_2") (pintype "passive"))
      (node (ref "U102") (pin "5") (pinfunction "OUT_B_5") (pintype "passive"))
    )
    (net (code "74") (name "Net-(U103-OUT_A)") (class "Default")
      (node (ref "R117") (pin "2") (pinfunction "2_2") (pintype "passive"))
      (node (ref "U103") (pin "7") (pinfunction "OUT_A_7") (pintype "passive"))
    )
    (net (code "75") (name "Net-(U103-OUT_B)") (class "Default")
      (node (ref "R118") (pin "2") (pinfunction "2_2") (pintype "passive"))
      (node (ref "U103") (pin "5") (pinfunction "OUT_B_5") (pintype "passive"))
    )
    (net (code "76") (name "Net-(U104-OUT_A)") (class "Default")
      (node (ref "R123") (pin "2") (pinfunction "2_2") (pintype "passive"))
      (node (ref "U104") (pin "7") (pinfunction "OUT_A_7") (pintype "passive"))
    )
    (net (code "77") (name "Net-(U104-OUT_B)") (class "Default")
      (node (ref "R124") (pin "2") (pinfunction "2_2") (pintype "passive"))
      (node (ref "U104") (pin "5") (pinfunction "OUT_B_5") (pintype "passive"))
    )
    (net (code "78") (name "Net-(U105-OUT_A)") (class "Default")
      (node (ref "R129") (pin "2") (pinfunction "2_2") (pintype "passive"))
      (node (ref "U105") (pin "7") (pinfunction "OUT_A_7") (pintype "passive"))
    )
    (net (code "79") (name "Net-(U105-OUT_B)") (class "Default")
      (node (ref "R130") (pin "2") (pinfunction "2_2") (pintype "passive"))
      (node (ref "U105") (pin "5") (pinfunction "OUT_B_5") (pintype "passive"))
    )
    (net (code "80") (name "Net-(U106-OUT_A)") (class "Default")
      (node (ref "R135") (pin "2") (pinfunction "2_2") (pintype "passive"))
      (node (ref "U106") (pin "7") (pinfunction "OUT_A_7") (pintype "passive"))
    )
    (net (code "81") (name "Net-(U106-OUT_B)") (class "Default")
      (node (ref "R136") (pin "2") (pinfunction "2_2") (pintype "passive"))
      (node (ref "U106") (pin "5") (pinfunction "OUT_B_5") (pintype "passive"))
    )
    (net (code "82") (name "unconnected-(U101-NC-Pad1)") (class "Default")
      (node (ref "U101") (pin "1") (pinfunction "NC_1") (pintype "passive+no_connect"))
    )
    (net (code "83") (name "unconnected-(U101-NC-Pad8)") (class "Default")
      (node (ref "U101") (pin "8") (pinfunction "NC_8") (pintype "passive+no_connect"))
    )
    (net (code "84") (name "unconnected-(U102-NC-Pad1)") (class "Default")
      (node (ref "U102") (pin "1") (pinfunction "NC_1") (pintype "passive+no_connect"))
    )
    (net (code "85") (name "unconnected-(U102-NC-Pad8)") (class "Default")
      (node (ref "U102") (pin "8") (pinfunction "NC_8") (pintype "passive+no_connect"))
    )
    (net (code "86") (name "unconnected-(U103-NC-Pad1)") (class "Default")
      (node (ref "U103") (pin "1") (pinfunction "NC_1") (pintype "passive+no_connect"))
    )
    (net (code "87") (name "unconnected-(U103-NC-Pad8)") (class "Default")
      (node (ref "U103") (pin "8") (pinfunction "NC_8") (pintype "passive+no_connect"))
    )
    (net (code "88") (name "unconnected-(U104-NC-Pad1)") (class "Default")
      (node (ref "U104") (pin "1") (pinfunction "NC_1") (pintype "passive+no_connect"))
    )
    (net (code "89") (name "unconnected-(U104-NC-Pad8)") (class "Default")
      (node (ref "U104") (pin "8") (pinfunction "NC_8") (pintype "passive+no_connect"))
    )
    (net (code "90") (name "unconnected-(U105-NC-Pad1)") (class "Default")
      (node (ref "U105") (pin "1") (pinfunction "NC_1") (pintype "passive+no_connect"))
    )
    (net (code "91") (name "unconnected-(U105-NC-Pad8)") (class "Default")
      (node (ref "U105") (pin "8") (pinfunction "NC_8") (pintype "passive+no_connect"))
    )
    (net (code "92") (name "unconnected-(U106-NC-Pad1)") (class "Default")
      (node (ref "U106") (pin "1") (pinfunction "NC_1") (pintype "passive+no_connect"))
    )
    (net (code "93") (name "unconnected-(U106-NC-Pad8)") (class "Default")
      (node (ref "U106") (pin "8") (pinfunction "NC_8") (pintype "passive+no_connect"))
    )
  )
)
